# staff.net
KiCad netlist of a schematic drawn in EAGLE
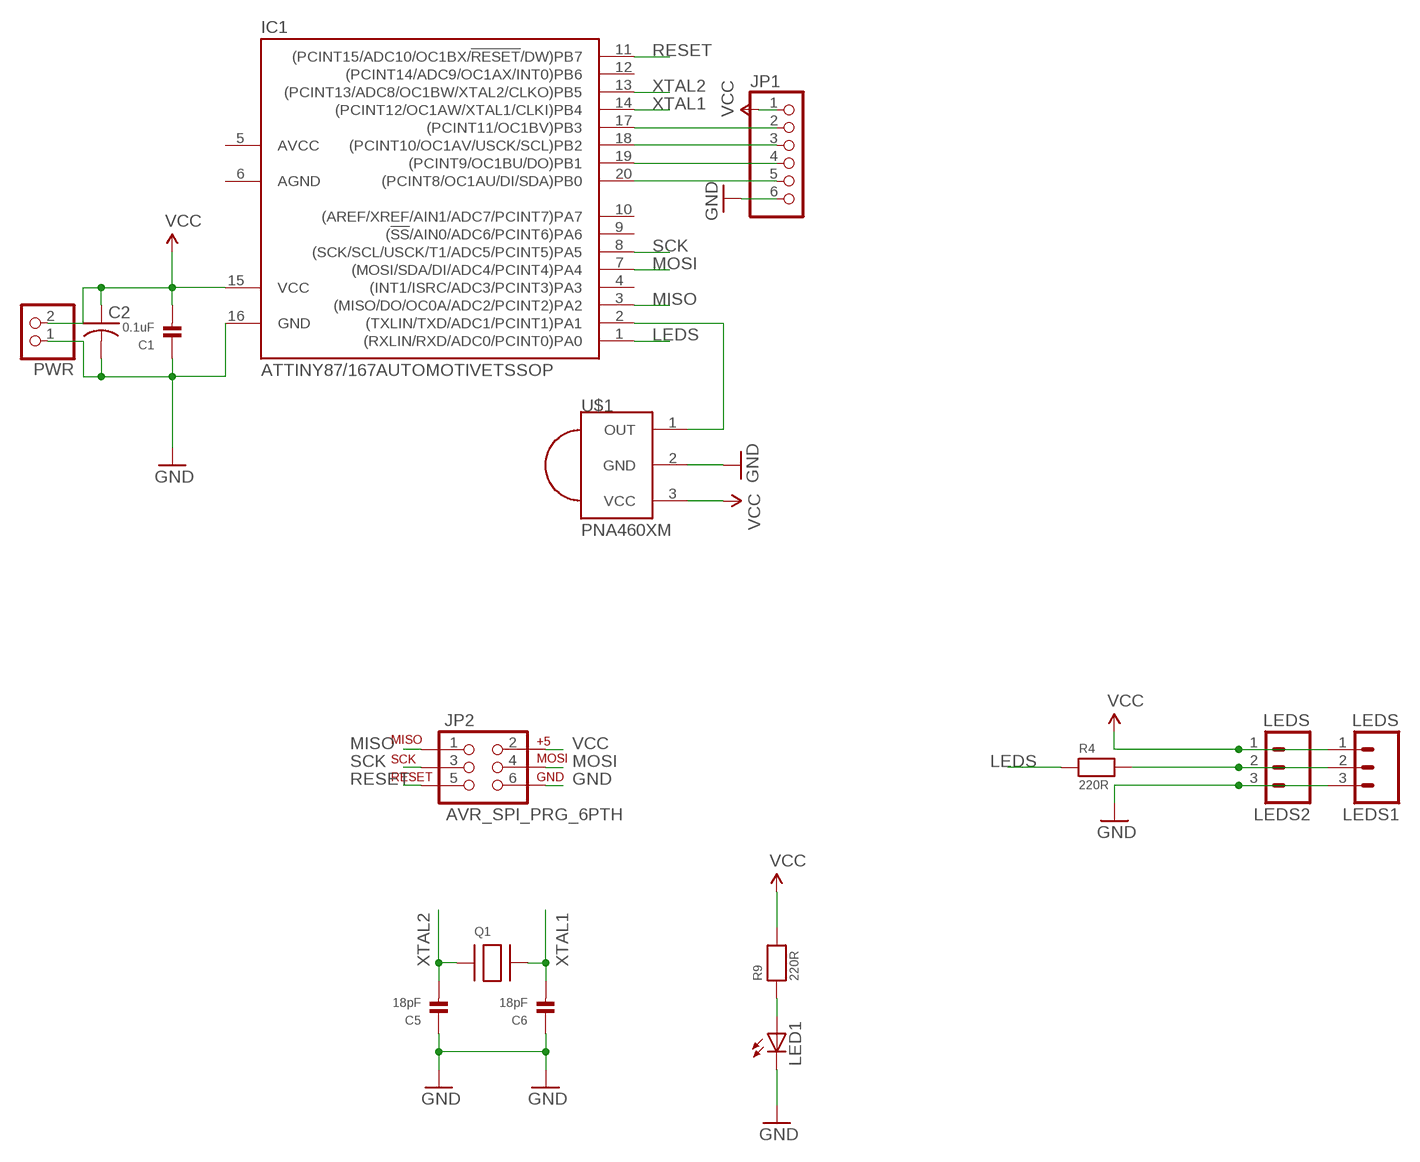
[diagram p0: schematic, sheet 1]

(export (version "E")
  (design (tool "Eeschema 10.0.6"))
  (components
    (comp (ref "C1")
      (value "0.1uF")
      (footprint "eagle-import:0603")
      (libsource (lib "eagle-import") (part "CAP_CERAMIC0603"))
    )
    (comp (ref "C2")
      (value "C-US025-025X050")
      (footprint "eagle-import:C025-025X050")
      (libsource (lib "eagle-import") (part "C-US025-025X050"))
    )
    (comp (ref "C5")
      (value "18pF")
      (footprint "eagle-import:0603")
      (libsource (lib "eagle-import") (part "CAP_CERAMIC0603"))
    )
    (comp (ref "C6")
      (value "18pF")
      (footprint "eagle-import:0603")
      (libsource (lib "eagle-import") (part "CAP_CERAMIC0603"))
    )
    (comp (ref "IC1")
      (value "ATTINY87/167AUTOMOTIVETSSOP")
      (footprint "eagle-import:TSSOP20")
      (libsource (lib "eagle-import") (part "ATTINY87/167AUTOMOTIVETSSOP"))
    )
    (comp (ref "JP1")
      (value "PINHD-1X6CLEAN")
      (footprint "eagle-import:1X06-CLEAN")
      (libsource (lib "eagle-import") (part "PINHD-1X6CLEAN"))
    )
    (comp (ref "JP2")
      (value "AVR_SPI_PRG_6PTH")
      (footprint "eagle-import:2X3")
      (libsource (lib "eagle-import") (part "AVR_SPI_PRG_6PTH"))
    )
    (comp (ref "LED1")
      (value "LEDCHIPLED_0603")
      (footprint "eagle-import:CHIPLED_0603")
      (libsource (lib "eagle-import") (part "LEDCHIPLED_0603"))
    )
    (comp (ref "LEDS1")
      (value "LEDS")
      (footprint "eagle-import:1X03")
      (libsource (lib "eagle-import") (part "M03PTH"))
    )
    (comp (ref "LEDS2")
      (value "LEDS")
      (footprint "eagle-import:1X03")
      (libsource (lib "eagle-import") (part "M03PTH"))
    )
    (comp (ref "PWR")
      (value "PINHD-1X2")
      (footprint "eagle-import:1X02")
      (libsource (lib "eagle-import") (part "PINHD-1X2"))
    )
    (comp (ref "Q1")
      (value "CRYSTAL")
      (footprint "eagle-import:ABLS7M2")
      (libsource (lib "eagle-import") (part "CRYSTAL"))
    )
    (comp (ref "R4")
      (value "220R")
      (footprint "eagle-import:0603")
      (libsource (lib "eagle-import") (part "RESISTOR0603"))
    )
    (comp (ref "R9")
      (value "220R")
      (footprint "eagle-import:0603")
      (libsource (lib "eagle-import") (part "RESISTOR0603"))
    )
    (comp (ref "U$1")
      (value "PNA460XM")
      (footprint "eagle-import:PNA460XM")
      (libsource (lib "eagle-import") (part "PNA460XM"))
    )
  )
  (nets
    (net (code "1") (name "/LEDS") (class "Default")
      (node (ref "IC1") (pin "1") (pinfunction "(RXLIN/RXD/ADC0/PCINT0)PA0_1") (pintype "bidirectional"))
      (node (ref "R4") (pin "1") (pinfunction "1_1") (pintype "passive"))
    )
    (net (code "2") (name "/MISO") (class "Default")
      (node (ref "IC1") (pin "3") (pinfunction "(MISO/DO/OC0A/ADC2/PCINT2)PA2_3") (pintype "bidirectional"))
      (node (ref "JP2") (pin "1") (pinfunction "1_1") (pintype "passive"))
    )
    (net (code "3") (name "/MOSI") (class "Default")
      (node (ref "IC1") (pin "7") (pinfunction "(MOSI/SDA/DI/ADC4/PCINT4)PA4_7") (pintype "bidirectional"))
      (node (ref "JP2") (pin "4") (pinfunction "4_4") (pintype "passive"))
    )
    (net (code "4") (name "/RESET") (class "Default")
      (node (ref "IC1") (pin "11") (pinfunction "(PCINT15/ADC10/OC1BX/~{RESET}/DW)PB7_11") (pintype "bidirectional"))
      (node (ref "JP2") (pin "5") (pinfunction "5_5") (pintype "passive"))
    )
    (net (code "5") (name "/SCK") (class "Default")
      (node (ref "IC1") (pin "8") (pinfunction "(SCK/SCL/USCK/T1/ADC5/PCINT5)PA5_8") (pintype "bidirectional"))
      (node (ref "JP2") (pin "3") (pinfunction "3_3") (pintype "passive"))
    )
    (net (code "6") (name "/XTAL1") (class "Default")
      (node (ref "C6") (pin "2") (pinfunction "P$2_2") (pintype "passive"))
      (node (ref "IC1") (pin "14") (pinfunction "(PCINT12/OC1AW/XTAL1/CLKI)PB4_14") (pintype "bidirectional"))
      (node (ref "Q1") (pin "P$2") (pinfunction "P$2_P$2") (pintype "bidirectional"))
    )
    (net (code "7") (name "/XTAL2") (class "Default")
      (node (ref "C5") (pin "2") (pinfunction "P$2_2") (pintype "passive"))
      (node (ref "IC1") (pin "13") (pinfunction "(PCINT13/ADC8/OC1BW/XTAL2/CLKO)PB5_13") (pintype "bidirectional"))
      (node (ref "Q1") (pin "P$1") (pinfunction "P$1_P$1") (pintype "bidirectional"))
    )
    (net (code "8") (name "GND") (class "Default")
      (node (ref "C1") (pin "1") (pinfunction "P$1_1") (pintype "passive"))
      (node (ref "C2") (pin "2") (pinfunction "2_2") (pintype "passive"))
      (node (ref "C5") (pin "1") (pinfunction "P$1_1") (pintype "passive"))
      (node (ref "C6") (pin "1") (pinfunction "P$1_1") (pintype "passive"))
      (node (ref "IC1") (pin "16") (pinfunction "GND_16") (pintype "power_in"))
      (node (ref "JP1") (pin "6") (pinfunction "6_6") (pintype "passive"))
      (node (ref "JP2") (pin "6") (pinfunction "6_6") (pintype "passive"))
      (node (ref "LED1") (pin "C") (pinfunction "C_C") (pintype "passive"))
      (node (ref "LEDS1") (pin "3") (pinfunction "3_3") (pintype "passive"))
      (node (ref "LEDS2") (pin "3") (pinfunction "3_3") (pintype "passive"))
      (node (ref "PWR") (pin "1") (pinfunction "1_1") (pintype "passive"))
      (node (ref "U$1") (pin "2") (pinfunction "GND_2") (pintype "power_in"))
    )
    (net (code "9") (name "Net-(IC1-(PCINT8{slash}OC1AU{slash}DI{slash}SDA)PB0)") (class "Default")
      (node (ref "IC1") (pin "20") (pinfunction "(PCINT8/OC1AU/DI/SDA)PB0_20") (pintype "bidirectional"))
      (node (ref "JP1") (pin "5") (pinfunction "5_5") (pintype "passive"))
    )
    (net (code "10") (name "Net-(IC1-(PCINT9{slash}OC1BU{slash}DO)PB1)") (class "Default")
      (node (ref "IC1") (pin "19") (pinfunction "(PCINT9/OC1BU/DO)PB1_19") (pintype "bidirectional"))
      (node (ref "JP1") (pin "4") (pinfunction "4_4") (pintype "passive"))
    )
    (net (code "11") (name "Net-(IC1-(PCINT10{slash}OC1AV{slash}USCK{slash}SCL)PB2)") (class "Default")
      (node (ref "IC1") (pin "18") (pinfunction "(PCINT10/OC1AV/USCK/SCL)PB2_18") (pintype "bidirectional"))
      (node (ref "JP1") (pin "3") (pinfunction "3_3") (pintype "passive"))
    )
    (net (code "12") (name "Net-(IC1-(PCINT11{slash}OC1BV)PB3)") (class "Default")
      (node (ref "IC1") (pin "17") (pinfunction "(PCINT11/OC1BV)PB3_17") (pintype "bidirectional"))
      (node (ref "JP1") (pin "2") (pinfunction "2_2") (pintype "passive"))
    )
    (net (code "13") (name "Net-(IC1-(TXLIN{slash}TXD{slash}ADC1{slash}PCINT1)PA1)") (class "Default")
      (node (ref "IC1") (pin "2") (pinfunction "(TXLIN/TXD/ADC1/PCINT1)PA1_2") (pintype "bidirectional"))
      (node (ref "U$1") (pin "1") (pinfunction "OUT_1") (pintype "output"))
    )
    (net (code "14") (name "Net-(LED1-PadA)") (class "Default")
      (node (ref "LED1") (pin "A") (pinfunction "A_A") (pintype "passive"))
      (node (ref "R9") (pin "1") (pinfunction "1_1") (pintype "passive"))
    )
    (net (code "15") (name "Net-(LEDS1-Pad2)") (class "Default")
      (node (ref "LEDS1") (pin "2") (pinfunction "2_2") (pintype "passive"))
      (node (ref "LEDS2") (pin "2") (pinfunction "2_2") (pintype "passive"))
      (node (ref "R4") (pin "2") (pinfunction "2_2") (pintype "passive"))
    )
    (net (code "16") (name "VCC") (class "Default")
      (node (ref "C1") (pin "2") (pinfunction "P$2_2") (pintype "passive"))
      (node (ref "C2") (pin "1") (pinfunction "1_1") (pintype "passive"))
      (node (ref "IC1") (pin "15") (pinfunction "VCC_15") (pintype "power_in"))
      (node (ref "JP1") (pin "1") (pinfunction "1_1") (pintype "passive"))
      (node (ref "JP2") (pin "2") (pinfunction "2_2") (pintype "passive"))
      (node (ref "LEDS1") (pin "1") (pinfunction "1_1") (pintype "passive"))
      (node (ref "LEDS2") (pin "1") (pinfunction "1_1") (pintype "passive"))
      (node (ref "PWR") (pin "2") (pinfunction "2_2") (pintype "passive"))
      (node (ref "R9") (pin "2") (pinfunction "2_2") (pintype "passive"))
      (node (ref "U$1") (pin "3") (pinfunction "VCC_3") (pintype "power_in"))
    )
    (net (code "17") (name "unconnected-(IC1-(AREF{slash}XREF{slash}AIN1{slash}ADC7{slash}PCINT7)PA7-Pad10)") (class "Default")
      (node (ref "IC1") (pin "10") (pinfunction "(AREF/XREF/AIN1/ADC7/PCINT7)PA7_10") (pintype "bidirectional"))
    )
    (net (code "18") (name "unconnected-(IC1-(INT1{slash}ISRC{slash}ADC3{slash}PCINT3)PA3-Pad4)") (class "Default")
      (node (ref "IC1") (pin "4") (pinfunction "(INT1/ISRC/ADC3/PCINT3)PA3_4") (pintype "bidirectional"))
    )
    (net (code "19") (name "unconnected-(IC1-(PCINT14{slash}ADC9{slash}OC1AX{slash}INT0)PB6-Pad12)") (class "Default")
      (node (ref "IC1") (pin "12") (pinfunction "(PCINT14/ADC9/OC1AX/INT0)PB6_12") (pintype "bidirectional"))
    )
    (net (code "20") (name "unconnected-(IC1-(~{SS}{slash}AIN0{slash}ADC6{slash}PCINT6)PA6-Pad9)") (class "Default")
      (node (ref "IC1") (pin "9") (pinfunction "(~{SS}/AIN0/ADC6/PCINT6)PA6_9") (pintype "bidirectional"))
    )
    (net (code "21") (name "unconnected-(IC1-AGND-Pad6)") (class "Default")
      (node (ref "IC1") (pin "6") (pinfunction "AGND_6") (pintype "bidirectional"))
    )
    (net (code "22") (name "unconnected-(IC1-AVCC-Pad5)") (class "Default")
      (node (ref "IC1") (pin "5") (pinfunction "AVCC_5") (pintype "bidirectional"))
    )
  )
)
